# Sheet1.net
KiCad netlist of a schematic drawn in Altium Designer
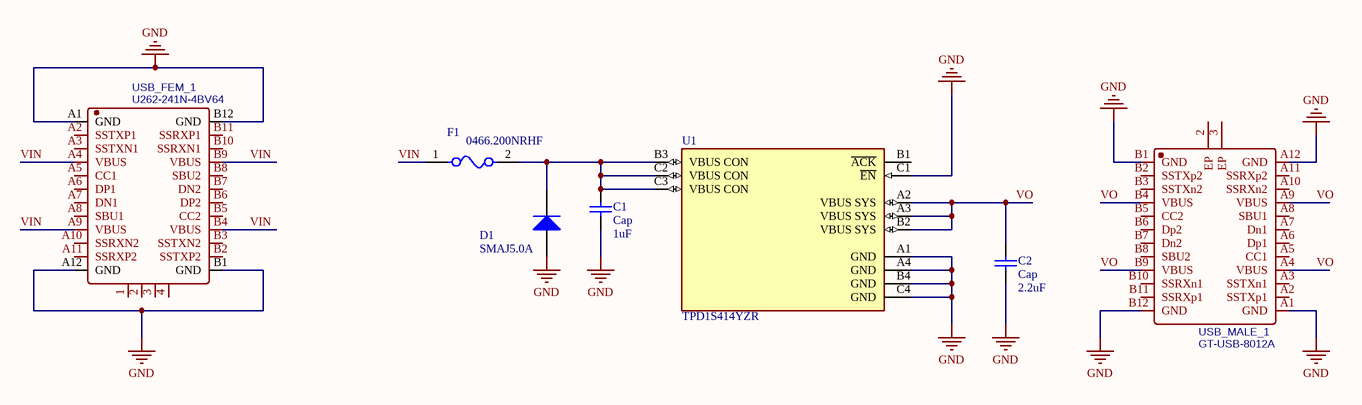
[diagram p0: Sheet1.SchDoc]

(export (version "E")
  (design (tool "Eeschema 10.0.6"))
  (components
    (comp (ref "C1")
      (value "Cap")
      (footprint "6-0805_N")
      (description "0805B105K500NT")
      (fields (field (name "ALTIUM_VALUE") "1uF") (field (name "PUBLISHER") "Altium Limited"))
      (libsource (lib "Miscellaneous Devices") (part "Cap"))
    )
    (comp (ref "C2")
      (value "Cap")
      (footprint "6-0805_N")
      (description "0805F225M500NT")
      (fields (field (name "ALTIUM_VALUE") "2.2uF") (field (name "PUBLISHER") "Altium Limited"))
      (libsource (lib "Miscellaneous Devices") (part "Cap"))
    )
    (comp (ref "D1")
      (value "SMAJ5.0A")
      (footprint "BOUR-SMA-2_V")
      (fields (field (name "MANUFACTURER") "Bourns"))
      (libsource (lib "Altium Content Vault") (part "D-AK-2"))
    )
    (comp (ref "F1")
      (value "0466.200NRHF")
      (footprint "FP-0466-MFG")
      (description "FUSE BOARD MNT 200MA 125VAC/VDC")
      (libsource (lib "Altium Content Vault") (part "5bcf9b9f640e542cf0359d10258e979"))
    )
    (comp (ref "U1")
      (value "TPD1S414YZR")
      (footprint "FP-YZ0012-C02-MFG")
      (description "IC PWR SWITCH N-CHAN 1:1 12DSBGA")
      (libsource (lib "Altium Content Vault") (part "e9321f069b7b23506881de3977d4215"))
    )
    (comp (ref "USB_FEM_1")
      (value "U262-241N-4BV64")
      (footprint "usbc-female")
      (description "Female USB-TYPE-C")
      (fields (field (name "BOM_SUPPLIER PART") "C388660") (field (name "CONTRIBUTOR") "LCSC"))
      (libsource (lib "altium-import") (part "root_0_U262-241N-4BV64_"))
    )
    (comp (ref "USB_MALE_1")
      (value "GT-USB-8012A")
      (footprint "PCBComponent_1")
      (description "MALE-USB-TYPE-C")
      (fields (field (name "BOM_SUPPLIER PART") "C2982483") (field (name "CONTRIBUTOR") "lcsc"))
      (libsource (lib "altium-import") (part "root_0_GT-USB-8012A_"))
    )
  )
  (nets
    (net (code "1") (name "/VIN") (class "Default")
      (node (ref "F1") (pin "1") (pinfunction "1_1") (pintype "passive"))
      (node (ref "USB_FEM_1") (pin "A4") (pinfunction "VBUS_A4") (pintype "passive"))
      (node (ref "USB_FEM_1") (pin "A9") (pinfunction "VBUS_A9") (pintype "passive"))
      (node (ref "USB_FEM_1") (pin "B4") (pinfunction "VBUS_B4") (pintype "passive"))
      (node (ref "USB_FEM_1") (pin "B9") (pinfunction "VBUS_B9") (pintype "passive"))
    )
    (net (code "2") (name "/VO") (class "Default")
      (node (ref "C2") (pin "2") (pinfunction "2_2") (pintype "passive"))
      (node (ref "U1") (pin "A2") (pinfunction "VBUS_SYS_A2") (pintype "bidirectional"))
      (node (ref "U1") (pin "A3") (pinfunction "VBUS_SYS_A3") (pintype "bidirectional"))
      (node (ref "U1") (pin "B2") (pinfunction "VBUS_SYS_B2") (pintype "bidirectional"))
      (node (ref "USB_MALE_1") (pin "A4") (pinfunction "VBUS_A4") (pintype "passive"))
      (node (ref "USB_MALE_1") (pin "A9") (pinfunction "VBUS_A9") (pintype "passive"))
      (node (ref "USB_MALE_1") (pin "B4") (pinfunction "VBUS_B4") (pintype "passive"))
      (node (ref "USB_MALE_1") (pin "B9") (pinfunction "VBUS_B9") (pintype "passive"))
    )
    (net (code "3") (name "GND") (class "Default")
      (node (ref "C1") (pin "1") (pinfunction "1_1") (pintype "passive"))
      (node (ref "C2") (pin "1") (pinfunction "1_1") (pintype "passive"))
      (node (ref "D1") (pin "1") (pinfunction "A_1") (pintype "passive"))
      (node (ref "U1") (pin "A1") (pinfunction "GND_A1") (pintype "power_in"))
      (node (ref "U1") (pin "A4") (pinfunction "GND_A4") (pintype "power_in"))
      (node (ref "U1") (pin "B4") (pinfunction "GND_B4") (pintype "power_in"))
      (node (ref "U1") (pin "C1") (pinfunction "~{EN}_C1") (pintype "input"))
      (node (ref "U1") (pin "C4") (pinfunction "GND_C4") (pintype "power_in"))
      (node (ref "USB_FEM_1") (pin "A1") (pinfunction "GND_A1") (pintype "passive"))
      (node (ref "USB_FEM_1") (pin "A12") (pinfunction "GND_A12") (pintype "passive"))
      (node (ref "USB_FEM_1") (pin "B1") (pinfunction "GND_B1") (pintype "passive"))
      (node (ref "USB_FEM_1") (pin "B12") (pinfunction "GND_B12") (pintype "passive"))
      (node (ref "USB_MALE_1") (pin "A1") (pinfunction "GND_A1") (pintype "passive"))
      (node (ref "USB_MALE_1") (pin "A12") (pinfunction "GND_A12") (pintype "passive"))
      (node (ref "USB_MALE_1") (pin "B1") (pinfunction "GND_B1") (pintype "passive"))
      (node (ref "USB_MALE_1") (pin "B12") (pinfunction "GND_B12") (pintype "passive"))
    )
    (net (code "4") (name "Net-(D1-K)") (class "Default")
      (node (ref "C1") (pin "2") (pinfunction "2_2") (pintype "passive"))
      (node (ref "D1") (pin "2") (pinfunction "K_2") (pintype "passive"))
      (node (ref "F1") (pin "2") (pinfunction "2_2") (pintype "passive"))
      (node (ref "U1") (pin "B3") (pinfunction "VBUS_CON_B3") (pintype "bidirectional"))
      (node (ref "U1") (pin "C2") (pinfunction "VBUS_CON_C2") (pintype "bidirectional"))
      (node (ref "U1") (pin "C3") (pinfunction "VBUS_CON_C3") (pintype "bidirectional"))
    )
    (net (code "5") (name "unconnected-(U1-~{ACK}-PadB1)") (class "Default")
      (node (ref "U1") (pin "B1") (pinfunction "~{ACK}_B1") (pintype "open_collector"))
    )
    (net (code "6") (name "unconnected-(USB_FEM_1-CC1-PadA5)") (class "Default")
      (node (ref "USB_FEM_1") (pin "A5") (pinfunction "CC1_A5") (pintype "passive"))
    )
    (net (code "7") (name "unconnected-(USB_FEM_1-CC2-PadB5)") (class "Default")
      (node (ref "USB_FEM_1") (pin "B5") (pinfunction "CC2_B5") (pintype "passive"))
    )
    (net (code "8") (name "unconnected-(USB_FEM_1-DN1-PadA7)") (class "Default")
      (node (ref "USB_FEM_1") (pin "A7") (pinfunction "DN1_A7") (pintype "passive"))
    )
    (net (code "9") (name "unconnected-(USB_FEM_1-DN2-PadB7)") (class "Default")
      (node (ref "USB_FEM_1") (pin "B7") (pinfunction "DN2_B7") (pintype "passive"))
    )
    (net (code "10") (name "unconnected-(USB_FEM_1-DP1-PadA6)") (class "Default")
      (node (ref "USB_FEM_1") (pin "A6") (pinfunction "DP1_A6") (pintype "passive"))
    )
    (net (code "11") (name "unconnected-(USB_FEM_1-DP2-PadB6)") (class "Default")
      (node (ref "USB_FEM_1") (pin "B6") (pinfunction "DP2_B6") (pintype "passive"))
    )
    (net (code "12") (name "unconnected-(USB_FEM_1-Pad1)") (class "Default")
      (node (ref "USB_FEM_1") (pin "1") (pinfunction "1_1") (pintype "passive"))
    )
    (net (code "13") (name "unconnected-(USB_FEM_1-Pad2)") (class "Default")
      (node (ref "USB_FEM_1") (pin "2") (pinfunction "2_2") (pintype "passive"))
    )
    (net (code "14") (name "unconnected-(USB_FEM_1-Pad3)") (class "Default")
      (node (ref "USB_FEM_1") (pin "3") (pinfunction "3_3") (pintype "passive"))
    )
    (net (code "15") (name "unconnected-(USB_FEM_1-Pad4)") (class "Default")
      (node (ref "USB_FEM_1") (pin "4") (pinfunction "4_4") (pintype "passive"))
    )
    (net (code "16") (name "unconnected-(USB_FEM_1-SBU1-PadA8)") (class "Default")
      (node (ref "USB_FEM_1") (pin "A8") (pinfunction "SBU1_A8") (pintype "passive"))
    )
    (net (code "17") (name "unconnected-(USB_FEM_1-SBU2-PadB8)") (class "Default")
      (node (ref "USB_FEM_1") (pin "B8") (pinfunction "SBU2_B8") (pintype "passive"))
    )
    (net (code "18") (name "unconnected-(USB_FEM_1-SSRXN1-PadB10)") (class "Default")
      (node (ref "USB_FEM_1") (pin "B10") (pinfunction "SSRXN1_B10") (pintype "passive"))
    )
    (net (code "19") (name "unconnected-(USB_FEM_1-SSRXN2-PadA10)") (class "Default")
      (node (ref "USB_FEM_1") (pin "A10") (pinfunction "SSRXN2_A10") (pintype "passive"))
    )
    (net (code "20") (name "unconnected-(USB_FEM_1-SSRXP1-PadB11)") (class "Default")
      (node (ref "USB_FEM_1") (pin "B11") (pinfunction "SSRXP1_B11") (pintype "passive"))
    )
    (net (code "21") (name "unconnected-(USB_FEM_1-SSRXP2-PadA11)") (class "Default")
      (node (ref "USB_FEM_1") (pin "A11") (pinfunction "SSRXP2_A11") (pintype "passive"))
    )
    (net (code "22") (name "unconnected-(USB_FEM_1-SSTXN1-PadA3)") (class "Default")
      (node (ref "USB_FEM_1") (pin "A3") (pinfunction "SSTXN1_A3") (pintype "passive"))
    )
    (net (code "23") (name "unconnected-(USB_FEM_1-SSTXN2-PadB3)") (class "Default")
      (node (ref "USB_FEM_1") (pin "B3") (pinfunction "SSTXN2_B3") (pintype "passive"))
    )
    (net (code "24") (name "unconnected-(USB_FEM_1-SSTXP1-PadA2)") (class "Default")
      (node (ref "USB_FEM_1") (pin "A2") (pinfunction "SSTXP1_A2") (pintype "passive"))
    )
    (net (code "25") (name "unconnected-(USB_FEM_1-SSTXP2-PadB2)") (class "Default")
      (node (ref "USB_FEM_1") (pin "B2") (pinfunction "SSTXP2_B2") (pintype "passive"))
    )
    (net (code "26") (name "unconnected-(USB_MALE_1-CC1-PadA5)") (class "Default")
      (node (ref "USB_MALE_1") (pin "A5") (pinfunction "CC1_A5") (pintype "passive"))
    )
    (net (code "27") (name "unconnected-(USB_MALE_1-CC2-PadB5)") (class "Default")
      (node (ref "USB_MALE_1") (pin "B5") (pinfunction "CC2_B5") (pintype "passive"))
    )
    (net (code "28") (name "unconnected-(USB_MALE_1-Dn1-PadA7)") (class "Default")
      (node (ref "USB_MALE_1") (pin "A7") (pinfunction "Dn1_A7") (pintype "passive"))
    )
    (net (code "29") (name "unconnected-(USB_MALE_1-Dn2-PadB7)") (class "Default")
      (node (ref "USB_MALE_1") (pin "B7") (pinfunction "Dn2_B7") (pintype "passive"))
    )
    (net (code "30") (name "unconnected-(USB_MALE_1-Dp1-PadA6)") (class "Default")
      (node (ref "USB_MALE_1") (pin "A6") (pinfunction "Dp1_A6") (pintype "passive"))
    )
    (net (code "31") (name "unconnected-(USB_MALE_1-Dp2-PadB6)") (class "Default")
      (node (ref "USB_MALE_1") (pin "B6") (pinfunction "Dp2_B6") (pintype "passive"))
    )
    (net (code "32") (name "unconnected-(USB_MALE_1-EP-Pad2)") (class "Default")
      (node (ref "USB_MALE_1") (pin "2") (pinfunction "EP_2") (pintype "passive"))
    )
    (net (code "33") (name "unconnected-(USB_MALE_1-EP-Pad3)") (class "Default")
      (node (ref "USB_MALE_1") (pin "3") (pinfunction "EP_3") (pintype "passive"))
    )
    (net (code "34") (name "unconnected-(USB_MALE_1-SBU1-PadA8)") (class "Default")
      (node (ref "USB_MALE_1") (pin "A8") (pinfunction "SBU1_A8") (pintype "passive"))
    )
    (net (code "35") (name "unconnected-(USB_MALE_1-SBU2-PadB8)") (class "Default")
      (node (ref "USB_MALE_1") (pin "B8") (pinfunction "SBU2_B8") (pintype "passive"))
    )
    (net (code "36") (name "unconnected-(USB_MALE_1-SSRXn1-PadB10)") (class "Default")
      (node (ref "USB_MALE_1") (pin "B10") (pinfunction "SSRXn1_B10") (pintype "passive"))
    )
    (net (code "37") (name "unconnected-(USB_MALE_1-SSRXn2-PadA10)") (class "Default")
      (node (ref "USB_MALE_1") (pin "A10") (pinfunction "SSRXn2_A10") (pintype "passive"))
    )
    (net (code "38") (name "unconnected-(USB_MALE_1-SSRXp1-PadB11)") (class "Default")
      (node (ref "USB_MALE_1") (pin "B11") (pinfunction "SSRXp1_B11") (pintype "passive"))
    )
    (net (code "39") (name "unconnected-(USB_MALE_1-SSRXp2-PadA11)") (class "Default")
      (node (ref "USB_MALE_1") (pin "A11") (pinfunction "SSRXp2_A11") (pintype "passive"))
    )
    (net (code "40") (name "unconnected-(USB_MALE_1-SSTXn1-PadA3)") (class "Default")
      (node (ref "USB_MALE_1") (pin "A3") (pinfunction "SSTXn1_A3") (pintype "passive"))
    )
    (net (code "41") (name "unconnected-(USB_MALE_1-SSTXn2-PadB3)") (class "Default")
      (node (ref "USB_MALE_1") (pin "B3") (pinfunction "SSTXn2_B3") (pintype "passive"))
    )
    (net (code "42") (name "unconnected-(USB_MALE_1-SSTXp1-PadA2)") (class "Default")
      (node (ref "USB_MALE_1") (pin "A2") (pinfunction "SSTXp1_A2") (pintype "passive"))
    )
    (net (code "43") (name "unconnected-(USB_MALE_1-SSTXp2-PadB2)") (class "Default")
      (node (ref "USB_MALE_1") (pin "B2") (pinfunction "SSTXp2_B2") (pintype "passive"))
    )
  )
)
